# M_H_ext_sound.net
KiCad netlist of a schematic drawn in EAGLE
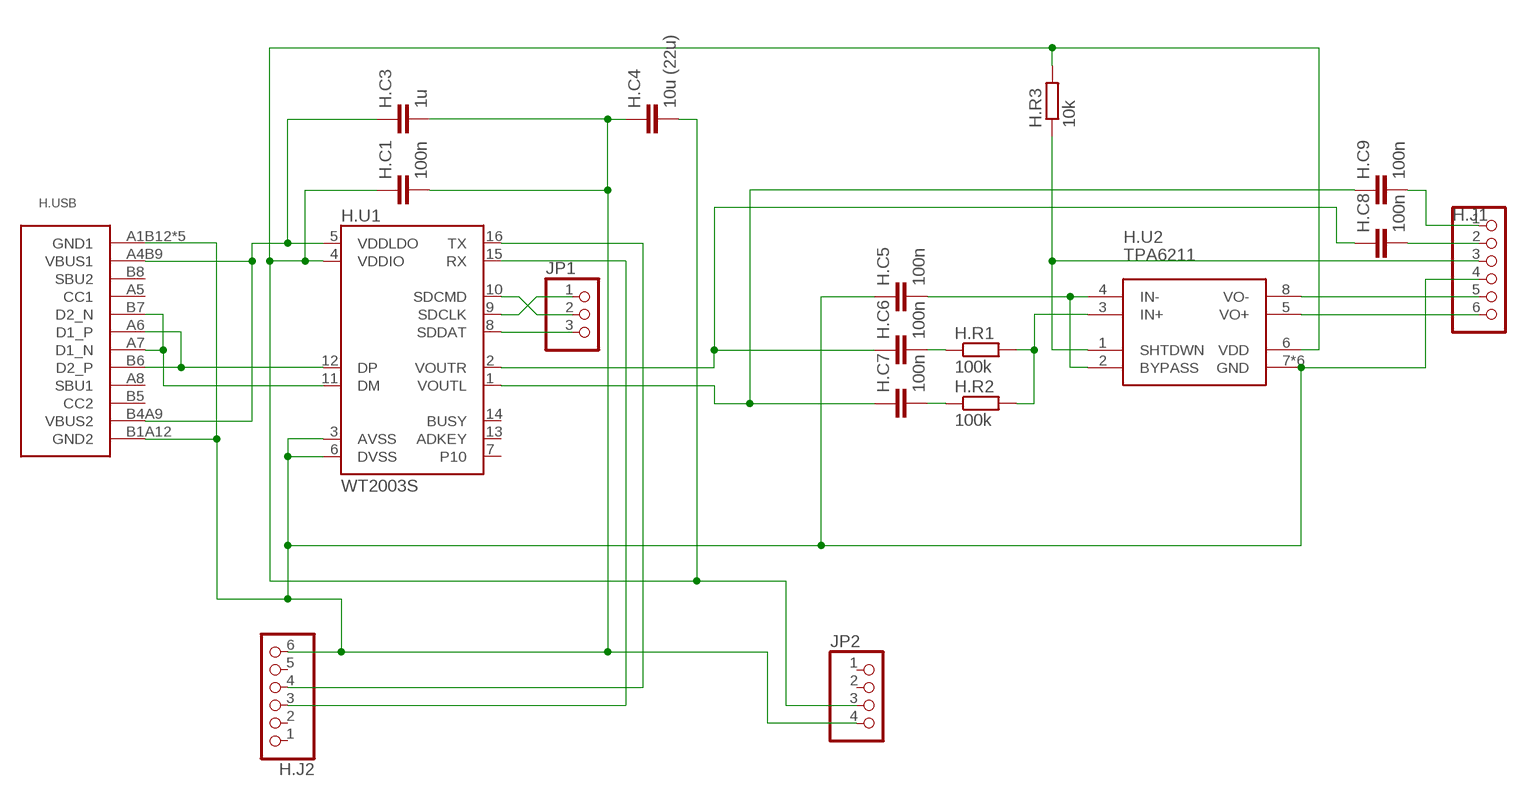
[diagram p0: schematic, sheet 1]

(export (version "E")
  (design (tool "Eeschema 10.0.6"))
  (components
    (comp (ref "H.C1")
      (value "100n")
      (footprint "eagle-import:C0603")
      (libsource (lib "eagle-import") (part "C-EUC0603"))
    )
    (comp (ref "H.C3")
      (value "1u")
      (footprint "eagle-import:C0603")
      (libsource (lib "eagle-import") (part "C-EUC0603"))
    )
    (comp (ref "H.C4")
      (value "10u (22u)")
      (footprint "eagle-import:C0805")
      (libsource (lib "eagle-import") (part "C-EUC0805"))
    )
    (comp (ref "H.C5")
      (value "100n")
      (footprint "eagle-import:C0603")
      (libsource (lib "eagle-import") (part "C-EUC0603"))
    )
    (comp (ref "H.C6")
      (value "100n")
      (footprint "eagle-import:C0603")
      (libsource (lib "eagle-import") (part "C-EUC0603"))
    )
    (comp (ref "H.C7")
      (value "100n")
      (footprint "eagle-import:C0603")
      (libsource (lib "eagle-import") (part "C-EUC0603"))
    )
    (comp (ref "H.C8")
      (value "100n")
      (footprint "eagle-import:C0603")
      (libsource (lib "eagle-import") (part "C-EUC0603"))
    )
    (comp (ref "H.C9")
      (value "100n")
      (footprint "eagle-import:C0603")
      (libsource (lib "eagle-import") (part "C-EUC0603"))
    )
    (comp (ref "H.J1")
      (value "PINHD-1X6")
      (footprint "eagle-import:1X06")
      (libsource (lib "eagle-import") (part "PINHD-1X6"))
    )
    (comp (ref "H.J2")
      (value "PINHD-1X6")
      (footprint "eagle-import:1X06")
      (libsource (lib "eagle-import") (part "PINHD-1X6"))
    )
    (comp (ref "H.R1")
      (value "100k")
      (footprint "eagle-import:R0603")
      (libsource (lib "eagle-import") (part "R-EU_R0603"))
    )
    (comp (ref "H.R2")
      (value "100k")
      (footprint "eagle-import:R0603")
      (libsource (lib "eagle-import") (part "R-EU_R0603"))
    )
    (comp (ref "H.R3")
      (value "10k")
      (footprint "eagle-import:R0603")
      (libsource (lib "eagle-import") (part "R-EU_R0603"))
    )
    (comp (ref "H.U1")
      (value "WT2003S")
      (footprint "eagle-import:SO16")
      (libsource (lib "eagle-import") (part "WT2003S"))
    )
    (comp (ref "H.U2")
      (value "TPA6211")
      (footprint "eagle-import:MSOP-POWERPAD-8")
      (libsource (lib "eagle-import") (part "TPA6211"))
    )
    (comp (ref "H.USB")
      (value "USB-C")
      (footprint "eagle-import:USB-C")
      (libsource (lib "eagle-import") (part "USB-C"))
    )
    (comp (ref "JP1")
      (value "PINHD-1X3")
      (footprint "eagle-import:1X03")
      (libsource (lib "eagle-import") (part "PINHD-1X3"))
    )
    (comp (ref "JP2")
      (value "PINHD-1X4")
      (footprint "eagle-import:1X04")
      (libsource (lib "eagle-import") (part "PINHD-1X4"))
    )
  )
  (nets
    (net (code "1") (name "Net-(H.C6-Pad2)") (class "Default")
      (node (ref "H.C6") (pin "2") (pinfunction "2_2") (pintype "passive"))
      (node (ref "H.R1") (pin "1") (pinfunction "1_1") (pintype "passive"))
    )
    (net (code "2") (name "Net-(H.C7-Pad2)") (class "Default")
      (node (ref "H.C7") (pin "2") (pinfunction "2_2") (pintype "passive"))
      (node (ref "H.R2") (pin "1") (pinfunction "1_1") (pintype "passive"))
    )
    (net (code "3") (name "Net-(H.C8-Pad2)") (class "Default")
      (node (ref "H.C8") (pin "2") (pinfunction "2_2") (pintype "passive"))
      (node (ref "H.J1") (pin "2") (pinfunction "2_2") (pintype "passive"))
    )
    (net (code "4") (name "Net-(H.C9-Pad2)") (class "Default")
      (node (ref "H.C9") (pin "2") (pinfunction "2_2") (pintype "passive"))
      (node (ref "H.J1") (pin "1") (pinfunction "1_1") (pintype "passive"))
    )
    (net (code "5") (name "Net-(H.U1-AVSS)") (class "Default")
      (node (ref "H.C1") (pin "2") (pinfunction "2_2") (pintype "passive"))
      (node (ref "H.C3") (pin "2") (pinfunction "2_2") (pintype "passive"))
      (node (ref "H.C4") (pin "1") (pinfunction "1_1") (pintype "passive"))
      (node (ref "H.C5") (pin "1") (pinfunction "1_1") (pintype "passive"))
      (node (ref "H.J1") (pin "4") (pinfunction "4_4") (pintype "passive"))
      (node (ref "H.J2") (pin "6") (pinfunction "6_6") (pintype "passive"))
      (node (ref "H.U1") (pin "3") (pinfunction "AVSS_3") (pintype "bidirectional"))
      (node (ref "H.U1") (pin "6") (pinfunction "DVSS_6") (pintype "bidirectional"))
      (node (ref "H.U2") (pin "7") (pinfunction "GND_7") (pintype "bidirectional"))
      (node (ref "H.U2") (pin "9") (pinfunction "GND_9") (pintype "bidirectional"))
      (node (ref "H.U2") (pin "P$10") (pinfunction "GND_P$10") (pintype "bidirectional"))
      (node (ref "H.U2") (pin "P$11") (pinfunction "GND_P$11") (pintype "bidirectional"))
      (node (ref "H.U2") (pin "P$12") (pinfunction "GND_P$12") (pintype "bidirectional"))
      (node (ref "H.U2") (pin "P$13") (pinfunction "GND_P$13") (pintype "bidirectional"))
      (node (ref "H.USB") (pin "A1B12") (pinfunction "GND1_A1B12") (pintype "bidirectional"))
      (node (ref "H.USB") (pin "B1A12") (pinfunction "GND2_B1A12") (pintype "bidirectional"))
      (node (ref "H.USB") (pin "SH1") (pinfunction "GND1_SH1") (pintype "bidirectional"))
      (node (ref "H.USB") (pin "SH2") (pinfunction "GND1_SH2") (pintype "bidirectional"))
      (node (ref "H.USB") (pin "SH3") (pinfunction "GND1_SH3") (pintype "bidirectional"))
      (node (ref "H.USB") (pin "SH4") (pinfunction "GND1_SH4") (pintype "bidirectional"))
      (node (ref "JP2") (pin "4") (pinfunction "4_4") (pintype "passive"))
    )
    (net (code "6") (name "Net-(H.U1-DM)") (class "Default")
      (node (ref "H.U1") (pin "11") (pinfunction "DM_11") (pintype "bidirectional"))
      (node (ref "H.USB") (pin "A7") (pinfunction "D1_N_A7") (pintype "bidirectional"))
      (node (ref "H.USB") (pin "B7") (pinfunction "D2_N_B7") (pintype "bidirectional"))
    )
    (net (code "7") (name "Net-(H.U1-DP)") (class "Default")
      (node (ref "H.U1") (pin "12") (pinfunction "DP_12") (pintype "bidirectional"))
      (node (ref "H.USB") (pin "A6") (pinfunction "D1_P_A6") (pintype "bidirectional"))
      (node (ref "H.USB") (pin "B6") (pinfunction "D2_P_B6") (pintype "bidirectional"))
    )
    (net (code "8") (name "Net-(H.U1-RX)") (class "Default")
      (node (ref "H.J2") (pin "3") (pinfunction "3_3") (pintype "passive"))
      (node (ref "H.U1") (pin "15") (pinfunction "RX_15") (pintype "bidirectional"))
    )
    (net (code "9") (name "Net-(H.U1-SDCLK)") (class "Default")
      (node (ref "H.U1") (pin "9") (pinfunction "SDCLK_9") (pintype "bidirectional"))
      (node (ref "JP1") (pin "1") (pinfunction "1_1") (pintype "passive"))
    )
    (net (code "10") (name "Net-(H.U1-SDCMD)") (class "Default")
      (node (ref "H.U1") (pin "10") (pinfunction "SDCMD_10") (pintype "bidirectional"))
      (node (ref "JP1") (pin "2") (pinfunction "2_2") (pintype "passive"))
    )
    (net (code "11") (name "Net-(H.U1-SDDAT)") (class "Default")
      (node (ref "H.U1") (pin "8") (pinfunction "SDDAT_8") (pintype "bidirectional"))
      (node (ref "JP1") (pin "3") (pinfunction "3_3") (pintype "passive"))
    )
    (net (code "12") (name "Net-(H.U1-TX)") (class "Default")
      (node (ref "H.J2") (pin "4") (pinfunction "4_4") (pintype "passive"))
      (node (ref "H.U1") (pin "16") (pinfunction "TX_16") (pintype "bidirectional"))
    )
    (net (code "13") (name "Net-(H.U1-VDDIO)") (class "Default")
      (node (ref "H.C1") (pin "1") (pinfunction "1_1") (pintype "passive"))
      (node (ref "H.C4") (pin "2") (pinfunction "2_2") (pintype "passive"))
      (node (ref "H.R3") (pin "2") (pinfunction "2_2") (pintype "passive"))
      (node (ref "H.U1") (pin "4") (pinfunction "VDDIO_4") (pintype "bidirectional"))
      (node (ref "H.U2") (pin "6") (pinfunction "VDD_6") (pintype "bidirectional"))
      (node (ref "JP2") (pin "3") (pinfunction "3_3") (pintype "passive"))
    )
    (net (code "14") (name "Net-(H.U1-VDDLDO)") (class "Default")
      (node (ref "H.C3") (pin "1") (pinfunction "1_1") (pintype "passive"))
      (node (ref "H.U1") (pin "5") (pinfunction "VDDLDO_5") (pintype "bidirectional"))
      (node (ref "H.USB") (pin "A4B9") (pinfunction "VBUS1_A4B9") (pintype "bidirectional"))
      (node (ref "H.USB") (pin "B4A9") (pinfunction "VBUS2_B4A9") (pintype "bidirectional"))
    )
    (net (code "15") (name "Net-(H.U1-VOUTL)") (class "Default")
      (node (ref "H.C7") (pin "1") (pinfunction "1_1") (pintype "passive"))
      (node (ref "H.C9") (pin "1") (pinfunction "1_1") (pintype "passive"))
      (node (ref "H.U1") (pin "1") (pinfunction "VOUTL_1") (pintype "bidirectional"))
    )
    (net (code "16") (name "Net-(H.U1-VOUTR)") (class "Default")
      (node (ref "H.C6") (pin "1") (pinfunction "1_1") (pintype "passive"))
      (node (ref "H.C8") (pin "1") (pinfunction "1_1") (pintype "passive"))
      (node (ref "H.U1") (pin "2") (pinfunction "VOUTR_2") (pintype "bidirectional"))
    )
    (net (code "17") (name "Net-(H.U2-BYPASS)") (class "Default")
      (node (ref "H.C5") (pin "2") (pinfunction "2_2") (pintype "passive"))
      (node (ref "H.U2") (pin "2") (pinfunction "BYPASS_2") (pintype "bidirectional"))
      (node (ref "H.U2") (pin "4") (pinfunction "IN-_4") (pintype "bidirectional"))
    )
    (net (code "18") (name "Net-(H.U2-IN+)") (class "Default")
      (node (ref "H.R1") (pin "2") (pinfunction "2_2") (pintype "passive"))
      (node (ref "H.R2") (pin "2") (pinfunction "2_2") (pintype "passive"))
      (node (ref "H.U2") (pin "3") (pinfunction "IN+_3") (pintype "bidirectional"))
    )
    (net (code "19") (name "Net-(H.U2-SHTDWN)") (class "Default")
      (node (ref "H.J1") (pin "3") (pinfunction "3_3") (pintype "passive"))
      (node (ref "H.R3") (pin "1") (pinfunction "1_1") (pintype "passive"))
      (node (ref "H.U2") (pin "1") (pinfunction "SHTDWN_1") (pintype "bidirectional"))
    )
    (net (code "20") (name "Net-(H.U2-VO+)") (class "Default")
      (node (ref "H.J1") (pin "6") (pinfunction "6_6") (pintype "passive"))
      (node (ref "H.U2") (pin "5") (pinfunction "VO+_5") (pintype "bidirectional"))
    )
    (net (code "21") (name "Net-(H.U2-VO-)") (class "Default")
      (node (ref "H.J1") (pin "5") (pinfunction "5_5") (pintype "passive"))
      (node (ref "H.U2") (pin "8") (pinfunction "VO-_8") (pintype "bidirectional"))
    )
    (net (code "22") (name "unconnected-(H.J2-Pad1)") (class "Default")
      (node (ref "H.J2") (pin "1") (pinfunction "1_1") (pintype "passive"))
    )
    (net (code "23") (name "unconnected-(H.J2-Pad2)") (class "Default")
      (node (ref "H.J2") (pin "2") (pinfunction "2_2") (pintype "passive"))
    )
    (net (code "24") (name "unconnected-(H.J2-Pad5)") (class "Default")
      (node (ref "H.J2") (pin "5") (pinfunction "5_5") (pintype "passive"))
    )
    (net (code "25") (name "unconnected-(H.U1-ADKEY-Pad13)") (class "Default")
      (node (ref "H.U1") (pin "13") (pinfunction "ADKEY_13") (pintype "bidirectional"))
    )
    (net (code "26") (name "unconnected-(H.U1-BUSY-Pad14)") (class "Default")
      (node (ref "H.U1") (pin "14") (pinfunction "BUSY_14") (pintype "bidirectional"))
    )
    (net (code "27") (name "unconnected-(H.U1-P10-Pad7)") (class "Default")
      (node (ref "H.U1") (pin "7") (pinfunction "P10_7") (pintype "bidirectional"))
    )
    (net (code "28") (name "unconnected-(H.USB-CC1-PadA5)") (class "Default")
      (node (ref "H.USB") (pin "A5") (pinfunction "CC1_A5") (pintype "bidirectional"))
    )
    (net (code "29") (name "unconnected-(H.USB-CC2-PadB5)") (class "Default")
      (node (ref "H.USB") (pin "B5") (pinfunction "CC2_B5") (pintype "bidirectional"))
    )
    (net (code "30") (name "unconnected-(H.USB-SBU1-PadA8)") (class "Default")
      (node (ref "H.USB") (pin "A8") (pinfunction "SBU1_A8") (pintype "bidirectional"))
    )
    (net (code "31") (name "unconnected-(H.USB-SBU2-PadB8)") (class "Default")
      (node (ref "H.USB") (pin "B8") (pinfunction "SBU2_B8") (pintype "bidirectional"))
    )
    (net (code "32") (name "unconnected-(JP2-Pad1)") (class "Default")
      (node (ref "JP2") (pin "1") (pinfunction "1_1") (pintype "passive"))
    )
    (net (code "33") (name "unconnected-(JP2-Pad2)") (class "Default")
      (node (ref "JP2") (pin "2") (pinfunction "2_2") (pintype "passive"))
    )
  )
)
